# 3_ADSTM32-Peripheral.net
KiCad netlist of a schematic drawn in Altium Designer
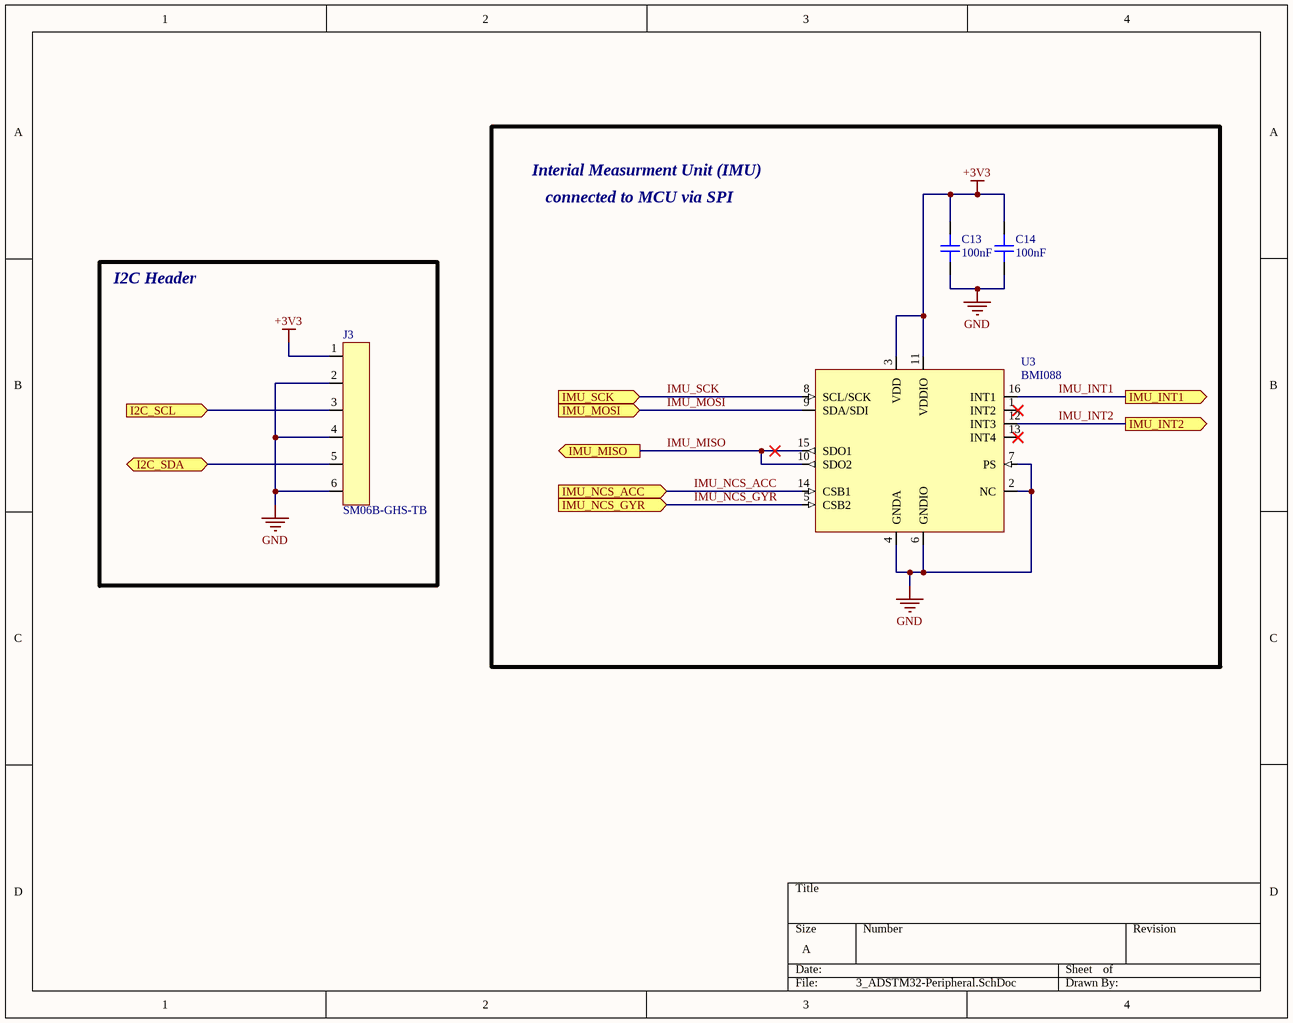
[diagram p0: 3_ADSTM32-Peripheral.SchDoc]

(export (version "E")
  (design (tool "Eeschema 10.0.6"))
  (components
    (comp (ref "C13")
      (value "100nF")
      (footprint "CAP_0603")
      (description "Capacitor SMD 0603")
      (libsource (lib "Schematic-Lib-PhilsLab") (part "CAP_0603"))
    )
    (comp (ref "C14")
      (value "100nF")
      (footprint "CAP_0603")
      (description "Capacitor SMD 0603")
      (libsource (lib "Schematic-Lib-PhilsLab") (part "CAP_0603"))
    )
    (comp (ref "J3")
      (value "SM06B-GHS-TB")
      (footprint "SM06B-GHS-TB")
      (description "Header Connector 6 Position 1.25MM Pitch SMD Horizontal JST GH")
      (fields (field (name "MANUFACTURER") "JST"))
      (libsource (lib "Schematic-Lib-PhilsLab") (part "SM06B-GHS-TB"))
    )
    (comp (ref "U3")
      (value "BMI088")
      (footprint "BMI088")
      (description "Inertial Measurement Unit IMU 6-Axis LGA")
      (fields (field (name "MANUFACTURER") "Bosch"))
      (libsource (lib "Schematic-Lib-PhilsLab") (part "BMI088"))
    )
  )
  (nets
    (net (code "1") (name "+3V3") (class "Default")
      (node (ref "C13") (pin "2") (pinfunction "2_2") (pintype "passive"))
      (node (ref "C14") (pin "2") (pinfunction "2_2") (pintype "passive"))
      (node (ref "J3") (pin "1") (pinfunction "1_1") (pintype "passive"))
      (node (ref "U3") (pin "11") (pinfunction "VDDIO_11") (pintype "power_in"))
      (node (ref "U3") (pin "3") (pinfunction "VDD_3") (pintype "power_in"))
    )
    (net (code "2") (name "/I2C_SCL") (class "Default")
      (node (ref "J3") (pin "3") (pinfunction "3_3") (pintype "passive"))
    )
    (net (code "3") (name "/I2C_SDA") (class "Default")
      (node (ref "J3") (pin "5") (pinfunction "5_5") (pintype "passive"))
    )
    (net (code "4") (name "/IMU_INT1") (class "Default")
      (node (ref "U3") (pin "16") (pinfunction "INT1_16") (pintype "bidirectional"))
    )
    (net (code "5") (name "/IMU_INT2") (class "Default")
      (node (ref "U3") (pin "12") (pinfunction "INT3_12") (pintype "bidirectional"))
    )
    (net (code "6") (name "/IMU_MISO") (class "Default")
      (node (ref "U3") (pin "10") (pinfunction "SDO2_10") (pintype "output"))
      (node (ref "U3") (pin "15") (pinfunction "SDO1_15") (pintype "output"))
    )
    (net (code "7") (name "/IMU_MOSI") (class "Default")
      (node (ref "U3") (pin "9") (pinfunction "SDA/SDI_9") (pintype "bidirectional"))
    )
    (net (code "8") (name "/IMU_NCS_ACC") (class "Default")
      (node (ref "U3") (pin "14") (pinfunction "CSB1_14") (pintype "input"))
    )
    (net (code "9") (name "/IMU_NCS_GYR") (class "Default")
      (node (ref "U3") (pin "5") (pinfunction "CSB2_5") (pintype "input"))
    )
    (net (code "10") (name "/IMU_SCK") (class "Default")
      (node (ref "U3") (pin "8") (pinfunction "SCL/SCK_8") (pintype "input"))
    )
    (net (code "11") (name "GND") (class "Default")
      (node (ref "C13") (pin "1") (pinfunction "1_1") (pintype "passive"))
      (node (ref "C14") (pin "1") (pinfunction "1_1") (pintype "passive"))
      (node (ref "J3") (pin "2") (pinfunction "2_2") (pintype "passive"))
      (node (ref "J3") (pin "4") (pinfunction "4_4") (pintype "passive"))
      (node (ref "J3") (pin "6") (pinfunction "6_6") (pintype "passive"))
      (node (ref "U3") (pin "2") (pinfunction "NC_2") (pintype "passive"))
      (node (ref "U3") (pin "4") (pinfunction "GNDA_4") (pintype "power_in"))
      (node (ref "U3") (pin "6") (pinfunction "GNDIO_6") (pintype "power_in"))
      (node (ref "U3") (pin "7") (pinfunction "PS_7") (pintype "input"))
    )
    (net (code "12") (name "unconnected-(U3-INT2-Pad1)") (class "Default")
      (node (ref "U3") (pin "1") (pinfunction "INT2_1") (pintype "bidirectional+no_connect"))
    )
    (net (code "13") (name "unconnected-(U3-INT4-Pad13)") (class "Default")
      (node (ref "U3") (pin "13") (pinfunction "INT4_13") (pintype "bidirectional+no_connect"))
    )
  )
)
